# dimmerWall.net
KiCad netlist of a schematic drawn in EAGLE
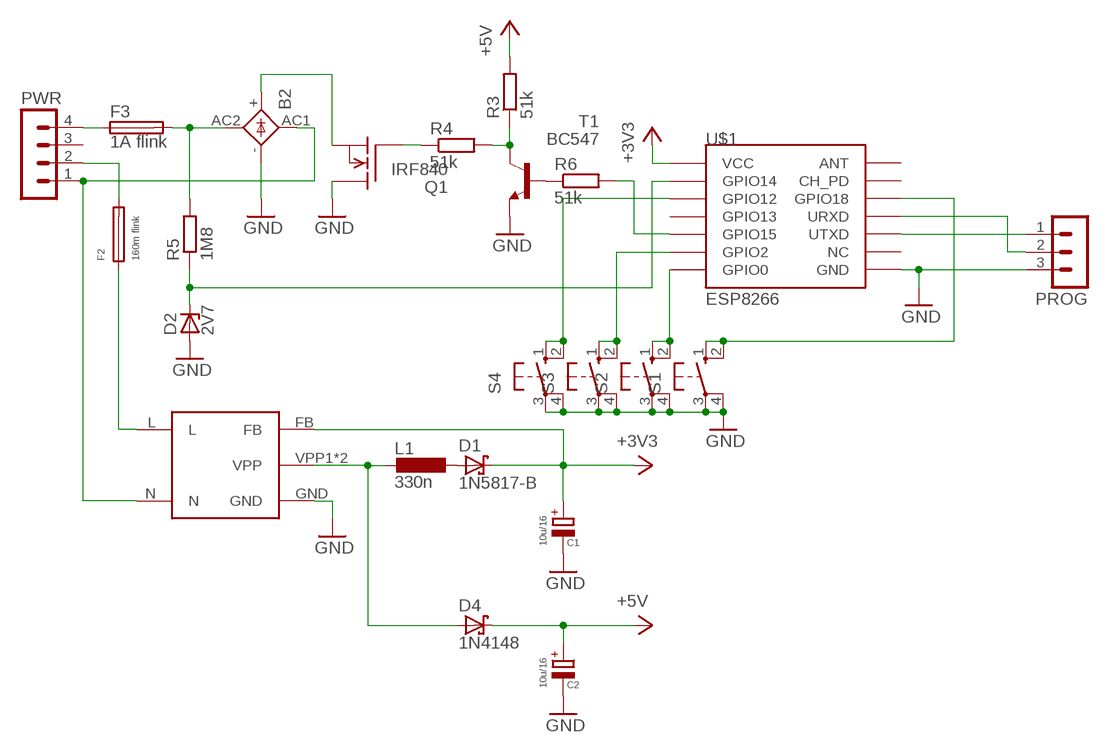
[diagram p0: schematic, sheet 1]

(export (version "E")
  (design (tool "Eeschema 10.0.6"))
  (components
    (comp (ref "B2")
      (value "2KBP")
      (footprint "eagle-import:2KBP")
      (libsource (lib "eagle-import") (part "2KBP"))
    )
    (comp (ref "C1")
      (value "10u/16")
      (footprint "eagle-import:TT2D4L")
      (libsource (lib "eagle-import") (part "CPOL-EUTT2D4L"))
    )
    (comp (ref "C2")
      (value "10u/16")
      (footprint "eagle-import:TT2D4L")
      (libsource (lib "eagle-import") (part "CPOL-EUTT2D4L"))
    )
    (comp (ref "D1")
      (value "1N5817-B")
      (footprint "eagle-import:DO41-7.6")
      (libsource (lib "eagle-import") (part "1N5817-B"))
    )
    (comp (ref "D2")
      (value "2V7")
      (footprint "eagle-import:DO34Z7")
      (libsource (lib "eagle-import") (part "ZENER-DIODEDO34-7"))
    )
    (comp (ref "D4")
      (value "1N4148")
      (footprint "eagle-import:DO41-7.6")
      (libsource (lib "eagle-import") (part "1N5817-B"))
    )
    (comp (ref "F2")
      (value "160m flink")
      (footprint "eagle-import:19560")
      (fields (field (name "MPN") "56000001009"))
      (libsource (lib "eagle-import") (part "19560"))
    )
    (comp (ref "F3")
      (value "1A flink")
      (footprint "eagle-import:SHK20L")
      (libsource (lib "eagle-import") (part "FUSESHK20L"))
    )
    (comp (ref "L1")
      (value "330n")
      (footprint "eagle-import:0204_5")
      (libsource (lib "eagle-import") (part "L-EU0204/5"))
    )
    (comp (ref "PROG")
      (value "MA03-1")
      (footprint "eagle-import:MA03-1")
      (libsource (lib "eagle-import") (part "MA03-1"))
    )
    (comp (ref "PWR")
      (value "MA04-1")
      (footprint "eagle-import:MA04-1")
      (libsource (lib "eagle-import") (part "MA04-1"))
    )
    (comp (ref "Q1")
      (value "IRF840")
      (footprint "eagle-import:TO220")
      (libsource (lib "eagle-import") (part "IRF840"))
    )
    (comp (ref "R3")
      (value "51k")
      (footprint "eagle-import:0207_12")
      (libsource (lib "eagle-import") (part "R-EU_0207/12"))
    )
    (comp (ref "R4")
      (value "51k")
      (footprint "eagle-import:0207_12")
      (libsource (lib "eagle-import") (part "R-EU_0207/12"))
    )
    (comp (ref "R5")
      (value "1M8")
      (footprint "eagle-import:0207_12")
      (libsource (lib "eagle-import") (part "R-EU_0207/12"))
    )
    (comp (ref "R6")
      (value "51k")
      (footprint "eagle-import:0207_12")
      (libsource (lib "eagle-import") (part "R-EU_0207/12"))
    )
    (comp (ref "S1")
      (value "10-XX")
      (footprint "eagle-import:B3F-10XX")
      (fields (field (name "MPN") "B3F-1000"))
      (libsource (lib "eagle-import") (part "10-XX"))
    )
    (comp (ref "S2")
      (value "10-XX")
      (footprint "eagle-import:B3F-10XX")
      (fields (field (name "MPN") "B3F-1000"))
      (libsource (lib "eagle-import") (part "10-XX"))
    )
    (comp (ref "S3")
      (value "10-XX")
      (footprint "eagle-import:B3F-10XX")
      (fields (field (name "MPN") "B3F-1000"))
      (libsource (lib "eagle-import") (part "10-XX"))
    )
    (comp (ref "S4")
      (value "10-XX")
      (footprint "eagle-import:B3F-10XX")
      (fields (field (name "MPN") "B3F-1000"))
      (libsource (lib "eagle-import") (part "10-XX"))
    )
    (comp (ref "T1")
      (value "BC547")
      (footprint "eagle-import:TO92")
      (libsource (lib "eagle-import") (part "BC547"))
    )
    (comp (ref "U$1")
      (value "ESP8266")
      (footprint "eagle-import:ESP-03")
      (libsource (lib "eagle-import") (part "ESP8266"))
    )
    (comp (ref "U$2")
      (value "SMPS")
      (footprint "eagle-import:SMPS")
      (libsource (lib "eagle-import") (part "SMPS"))
    )
  )
  (nets
    (net (code "1") (name "+3V3") (class "Default")
      (node (ref "C1") (pin "+") (pinfunction "+_+") (pintype "passive"))
      (node (ref "D1") (pin "C") (pinfunction "C_C") (pintype "passive"))
      (node (ref "U$1") (pin "VCC") (pinfunction "VCC_VCC") (pintype "bidirectional"))
      (node (ref "U$2") (pin "FB") (pinfunction "FB_FB") (pintype "bidirectional"))
    )
    (net (code "2") (name "+5V") (class "Default")
      (node (ref "C2") (pin "+") (pinfunction "+_+") (pintype "passive"))
      (node (ref "D4") (pin "C") (pinfunction "C_C") (pintype "passive"))
      (node (ref "R3") (pin "2") (pinfunction "2_2") (pintype "passive"))
    )
    (net (code "3") (name "GND") (class "Default")
      (node (ref "B2") (pin "-") (pinfunction "-_-") (pintype "passive"))
      (node (ref "C1") (pin "-") (pinfunction "-_-") (pintype "passive"))
      (node (ref "C2") (pin "-") (pinfunction "-_-") (pintype "passive"))
      (node (ref "D2") (pin "A") (pinfunction "A_A") (pintype "passive"))
      (node (ref "PROG") (pin "3") (pinfunction "3_3") (pintype "passive"))
      (node (ref "Q1") (pin "2") (pinfunction "D_2") (pintype "passive"))
      (node (ref "S1") (pin "3") (pinfunction "P_3") (pintype "passive"))
      (node (ref "S1") (pin "4") (pinfunction "P1_4") (pintype "passive"))
      (node (ref "S2") (pin "3") (pinfunction "P_3") (pintype "passive"))
      (node (ref "S2") (pin "4") (pinfunction "P1_4") (pintype "passive"))
      (node (ref "S3") (pin "3") (pinfunction "P_3") (pintype "passive"))
      (node (ref "S3") (pin "4") (pinfunction "P1_4") (pintype "passive"))
      (node (ref "S4") (pin "3") (pinfunction "P_3") (pintype "passive"))
      (node (ref "S4") (pin "4") (pinfunction "P1_4") (pintype "passive"))
      (node (ref "T1") (pin "1") (pinfunction "E_1") (pintype "passive"))
      (node (ref "U$1") (pin "GND") (pinfunction "GND_GND") (pintype "bidirectional"))
      (node (ref "U$2") (pin "GND") (pinfunction "GND_GND") (pintype "bidirectional"))
    )
    (net (code "4") (name "Net-(B2-PadAC1)") (class "Default")
      (node (ref "B2") (pin "AC1") (pinfunction "AC1_AC1") (pintype "passive"))
      (node (ref "PWR") (pin "1") (pinfunction "1_1") (pintype "passive"))
      (node (ref "U$2") (pin "N") (pinfunction "N_N") (pintype "bidirectional"))
    )
    (net (code "5") (name "Net-(D1-PadA)") (class "Default")
      (node (ref "D1") (pin "A") (pinfunction "A_A") (pintype "passive"))
      (node (ref "L1") (pin "1") (pinfunction "1_1") (pintype "passive"))
    )
    (net (code "6") (name "Net-(D2-PadC)") (class "Default")
      (node (ref "D2") (pin "C") (pinfunction "C_C") (pintype "passive"))
      (node (ref "R5") (pin "1") (pinfunction "1_1") (pintype "passive"))
      (node (ref "U$1") (pin "GPIO14") (pinfunction "GPIO14_GPIO14") (pintype "bidirectional"))
    )
    (net (code "7") (name "Net-(D4-PadA)") (class "Default")
      (node (ref "D4") (pin "A") (pinfunction "A_A") (pintype "passive"))
      (node (ref "L1") (pin "2") (pinfunction "2_2") (pintype "passive"))
      (node (ref "U$2") (pin "VPP1") (pinfunction "VPP_VPP1") (pintype "bidirectional"))
      (node (ref "U$2") (pin "VPP2") (pinfunction "VPP_VPP2") (pintype "bidirectional"))
    )
    (net (code "8") (name "Net-(F2-Pad1)") (class "Default")
      (node (ref "F2") (pin "1") (pinfunction "1_1") (pintype "passive"))
      (node (ref "U$2") (pin "L") (pinfunction "L_L") (pintype "bidirectional"))
    )
    (net (code "9") (name "Net-(F2-Pad2)") (class "Default")
      (node (ref "F2") (pin "2") (pinfunction "2_2") (pintype "passive"))
      (node (ref "PWR") (pin "2") (pinfunction "2_2") (pintype "passive"))
    )
    (net (code "10") (name "Net-(F3-1)") (class "Default")
      (node (ref "F3") (pin "1A") (pinfunction "1_1A") (pintype "passive"))
      (node (ref "PWR") (pin "4") (pinfunction "4_4") (pintype "passive"))
    )
    (net (code "11") (name "Net-(F3-2)") (class "Default")
      (node (ref "B2") (pin "AC2") (pinfunction "AC2_AC2") (pintype "passive"))
      (node (ref "F3") (pin "2A") (pinfunction "2_2A") (pintype "passive"))
      (node (ref "R5") (pin "2") (pinfunction "2_2") (pintype "passive"))
    )
    (net (code "12") (name "Net-(PROG-Pad1)") (class "Default")
      (node (ref "PROG") (pin "1") (pinfunction "1_1") (pintype "passive"))
      (node (ref "U$1") (pin "UTXD") (pinfunction "UTXD_UTXD") (pintype "bidirectional"))
    )
    (net (code "13") (name "Net-(PROG-Pad2)") (class "Default")
      (node (ref "PROG") (pin "2") (pinfunction "2_2") (pintype "passive"))
      (node (ref "U$1") (pin "URXD") (pinfunction "URXD_URXD") (pintype "bidirectional"))
    )
    (net (code "14") (name "Net-(Q1-G)") (class "Default")
      (node (ref "Q1") (pin "1") (pinfunction "G_1") (pintype "passive"))
      (node (ref "R4") (pin "1") (pinfunction "1_1") (pintype "passive"))
    )
    (net (code "15") (name "Net-(Q1-S)") (class "Default")
      (node (ref "B2") (pin "+") (pinfunction "+_+") (pintype "passive"))
      (node (ref "Q1") (pin "3") (pinfunction "S_3") (pintype "passive"))
    )
    (net (code "16") (name "Net-(R6-Pad2)") (class "Default")
      (node (ref "R6") (pin "2") (pinfunction "2_2") (pintype "passive"))
      (node (ref "U$1") (pin "GPIO15") (pinfunction "GPIO15_GPIO15") (pintype "bidirectional"))
    )
    (net (code "17") (name "Net-(S1-S)") (class "Default")
      (node (ref "S1") (pin "1") (pinfunction "S_1") (pintype "passive"))
      (node (ref "S1") (pin "2") (pinfunction "S1_2") (pintype "passive"))
      (node (ref "U$1") (pin "GPIO18") (pinfunction "GPIO18_GPIO18") (pintype "bidirectional"))
    )
    (net (code "18") (name "Net-(S2-S)") (class "Default")
      (node (ref "S2") (pin "1") (pinfunction "S_1") (pintype "passive"))
      (node (ref "S2") (pin "2") (pinfunction "S1_2") (pintype "passive"))
      (node (ref "U$1") (pin "GPIO0") (pinfunction "GPIO0_GPIO0") (pintype "bidirectional"))
    )
    (net (code "19") (name "Net-(S3-S)") (class "Default")
      (node (ref "S3") (pin "1") (pinfunction "S_1") (pintype "passive"))
      (node (ref "S3") (pin "2") (pinfunction "S1_2") (pintype "passive"))
      (node (ref "U$1") (pin "GPIO2") (pinfunction "GPIO2_GPIO2") (pintype "bidirectional"))
    )
    (net (code "20") (name "Net-(S4-S)") (class "Default")
      (node (ref "S4") (pin "1") (pinfunction "S_1") (pintype "passive"))
      (node (ref "S4") (pin "2") (pinfunction "S1_2") (pintype "passive"))
      (node (ref "U$1") (pin "GPIO12") (pinfunction "GPIO12_GPIO12") (pintype "bidirectional"))
    )
    (net (code "21") (name "Net-(T1-B)") (class "Default")
      (node (ref "R6") (pin "1") (pinfunction "1_1") (pintype "passive"))
      (node (ref "T1") (pin "2") (pinfunction "B_2") (pintype "passive"))
    )
    (net (code "22") (name "Net-(T1-C)") (class "Default")
      (node (ref "R3") (pin "1") (pinfunction "1_1") (pintype "passive"))
      (node (ref "R4") (pin "2") (pinfunction "2_2") (pintype "passive"))
      (node (ref "T1") (pin "3") (pinfunction "C_3") (pintype "passive"))
    )
    (net (code "23") (name "unconnected-(PWR-Pad3)") (class "Default")
      (node (ref "PWR") (pin "3") (pinfunction "3_3") (pintype "passive"))
    )
    (net (code "24") (name "unconnected-(U$1-PadANT)") (class "Default")
      (node (ref "U$1") (pin "ANT") (pinfunction "ANT_ANT") (pintype "bidirectional"))
    )
    (net (code "25") (name "unconnected-(U$1-PadCH_PD)") (class "Default")
      (node (ref "U$1") (pin "CH_PD") (pinfunction "CH_PD_CH_PD") (pintype "bidirectional"))
    )
    (net (code "26") (name "unconnected-(U$1-PadGPIO13)") (class "Default")
      (node (ref "U$1") (pin "GPIO13") (pinfunction "GPIO13_GPIO13") (pintype "bidirectional"))
    )
    (net (code "27") (name "unconnected-(U$1-PadNC)") (class "Default")
      (node (ref "U$1") (pin "NC") (pinfunction "NC_NC") (pintype "bidirectional"))
    )
  )
)
